# Low_Distortion_Oscillator_Amp2.net
KiCad netlist of a schematic drawn in Altium Designer
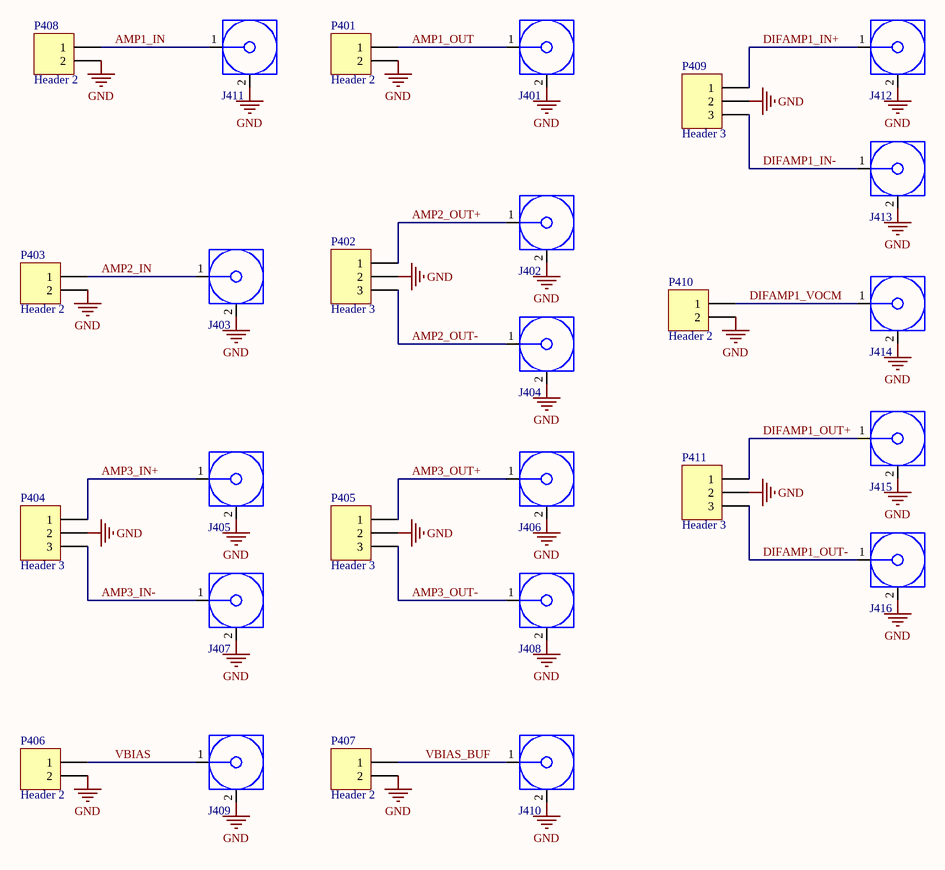
[diagram p0: Low Distortion Oscillator.Amp2.SchDoc]

(export (version "E")
  (design (tool "Eeschema 10.0.6"))
  (components
    (comp (ref "J401") (value "SMA") (footprint "SMA-2") (libsource (lib "carrot_lib") (part "SMA")))
    (comp (ref "J402") (value "SMA") (footprint "SMA-2") (libsource (lib "carrot_lib") (part "SMA")))
    (comp (ref "J403") (value "SMA") (footprint "SMA-2") (libsource (lib "carrot_lib") (part "SMA")))
    (comp (ref "J404") (value "SMA") (footprint "SMA-2") (libsource (lib "carrot_lib") (part "SMA")))
    (comp (ref "J405") (value "SMA") (footprint "SMA-2") (libsource (lib "carrot_lib") (part "SMA")))
    (comp (ref "J406") (value "SMA") (footprint "SMA-2") (libsource (lib "carrot_lib") (part "SMA")))
    (comp (ref "J407") (value "SMA") (footprint "SMA-2") (libsource (lib "carrot_lib") (part "SMA")))
    (comp (ref "J408") (value "SMA") (footprint "SMA-2") (libsource (lib "carrot_lib") (part "SMA")))
    (comp (ref "J409") (value "SMA") (footprint "SMA-2") (libsource (lib "carrot_lib") (part "SMA")))
    (comp (ref "J410") (value "SMA") (footprint "SMA-2") (libsource (lib "carrot_lib") (part "SMA")))
    (comp (ref "J411") (value "SMA") (footprint "SMA-2") (libsource (lib "carrot_lib") (part "SMA")))
    (comp (ref "J412") (value "SMA") (footprint "SMA-2") (libsource (lib "carrot_lib") (part "SMA")))
    (comp (ref "J413") (value "SMA") (footprint "SMA-2") (libsource (lib "carrot_lib") (part "SMA")))
    (comp (ref "J414") (value "SMA") (footprint "SMA-2") (libsource (lib "carrot_lib") (part "SMA")))
    (comp (ref "J415") (value "SMA") (footprint "SMA-2") (libsource (lib "carrot_lib") (part "SMA")))
    (comp (ref "J416") (value "SMA") (footprint "SMA-2") (libsource (lib "carrot_lib") (part "SMA")))
    (comp (ref "P401")
      (value "Header 2")
      (footprint "HDR1X2")
      (description "Header, 2-Pin")
      (libsource (lib "carrot_lib") (part "Header 2"))
    )
    (comp (ref "P402")
      (value "Header 3")
      (footprint "HDR1X3")
      (description "Header, 3-Pin")
      (libsource (lib "carrot_lib") (part "Header 3"))
    )
    (comp (ref "P403")
      (value "Header 2")
      (footprint "HDR1X2")
      (description "Header, 2-Pin")
      (libsource (lib "carrot_lib") (part "Header 2"))
    )
    (comp (ref "P404")
      (value "Header 3")
      (footprint "HDR1X3")
      (description "Header, 3-Pin")
      (libsource (lib "carrot_lib") (part "Header 3"))
    )
    (comp (ref "P405")
      (value "Header 3")
      (footprint "HDR1X3")
      (description "Header, 3-Pin")
      (libsource (lib "carrot_lib") (part "Header 3"))
    )
    (comp (ref "P406")
      (value "Header 2")
      (footprint "HDR1X2")
      (description "Header, 2-Pin")
      (libsource (lib "carrot_lib") (part "Header 2"))
    )
    (comp (ref "P407")
      (value "Header 2")
      (footprint "HDR1X2")
      (description "Header, 2-Pin")
      (libsource (lib "carrot_lib") (part "Header 2"))
    )
    (comp (ref "P408")
      (value "Header 2")
      (footprint "HDR1X2")
      (description "Header, 2-Pin")
      (libsource (lib "carrot_lib") (part "Header 2"))
    )
    (comp (ref "P409")
      (value "Header 3")
      (footprint "HDR1X3")
      (description "Header, 3-Pin")
      (libsource (lib "carrot_lib") (part "Header 3"))
    )
    (comp (ref "P410")
      (value "Header 2")
      (footprint "HDR1X2")
      (description "Header, 2-Pin")
      (libsource (lib "carrot_lib") (part "Header 2"))
    )
    (comp (ref "P411")
      (value "Header 3")
      (footprint "HDR1X3")
      (description "Header, 3-Pin")
      (libsource (lib "carrot_lib") (part "Header 3"))
    )
  )
  (nets
    (net (code "1") (name "/AMP1_IN") (class "Default")
      (node (ref "J411") (pin "1") (pinfunction "Signal_1") (pintype "power_in"))
      (node (ref "P408") (pin "1") (pinfunction "1_1") (pintype "passive"))
    )
    (net (code "2") (name "/AMP1_OUT") (class "Default")
      (node (ref "J401") (pin "1") (pinfunction "Signal_1") (pintype "power_in"))
      (node (ref "P401") (pin "1") (pinfunction "1_1") (pintype "passive"))
    )
    (net (code "3") (name "/AMP2_IN") (class "Default")
      (node (ref "J403") (pin "1") (pinfunction "Signal_1") (pintype "power_in"))
      (node (ref "P403") (pin "1") (pinfunction "1_1") (pintype "passive"))
    )
    (net (code "4") (name "/AMP2_OUT+") (class "Default")
      (node (ref "J402") (pin "1") (pinfunction "Signal_1") (pintype "power_in"))
      (node (ref "P402") (pin "1") (pinfunction "1_1") (pintype "passive"))
    )
    (net (code "5") (name "/AMP2_OUT-") (class "Default")
      (node (ref "J404") (pin "1") (pinfunction "Signal_1") (pintype "power_in"))
      (node (ref "P402") (pin "3") (pinfunction "3_3") (pintype "passive"))
    )
    (net (code "6") (name "/AMP3_IN+") (class "Default")
      (node (ref "J405") (pin "1") (pinfunction "Signal_1") (pintype "power_in"))
      (node (ref "P404") (pin "1") (pinfunction "1_1") (pintype "passive"))
    )
    (net (code "7") (name "/AMP3_IN-") (class "Default")
      (node (ref "J407") (pin "1") (pinfunction "Signal_1") (pintype "power_in"))
      (node (ref "P404") (pin "3") (pinfunction "3_3") (pintype "passive"))
    )
    (net (code "8") (name "/AMP3_OUT+") (class "Default")
      (node (ref "J406") (pin "1") (pinfunction "Signal_1") (pintype "power_in"))
      (node (ref "P405") (pin "1") (pinfunction "1_1") (pintype "passive"))
    )
    (net (code "9") (name "/AMP3_OUT-") (class "Default")
      (node (ref "J408") (pin "1") (pinfunction "Signal_1") (pintype "power_in"))
      (node (ref "P405") (pin "3") (pinfunction "3_3") (pintype "passive"))
    )
    (net (code "10") (name "/DIFAMP1_IN+") (class "Default")
      (node (ref "J412") (pin "1") (pinfunction "Signal_1") (pintype "power_in"))
      (node (ref "P409") (pin "1") (pinfunction "1_1") (pintype "passive"))
    )
    (net (code "11") (name "/DIFAMP1_IN-") (class "Default")
      (node (ref "J413") (pin "1") (pinfunction "Signal_1") (pintype "power_in"))
      (node (ref "P409") (pin "3") (pinfunction "3_3") (pintype "passive"))
    )
    (net (code "12") (name "/DIFAMP1_OUT+") (class "Default")
      (node (ref "J415") (pin "1") (pinfunction "Signal_1") (pintype "power_in"))
      (node (ref "P411") (pin "1") (pinfunction "1_1") (pintype "passive"))
    )
    (net (code "13") (name "/DIFAMP1_OUT-") (class "Default")
      (node (ref "J416") (pin "1") (pinfunction "Signal_1") (pintype "power_in"))
      (node (ref "P411") (pin "3") (pinfunction "3_3") (pintype "passive"))
    )
    (net (code "14") (name "/DIFAMP1_VOCM") (class "Default")
      (node (ref "J414") (pin "1") (pinfunction "Signal_1") (pintype "power_in"))
      (node (ref "P410") (pin "1") (pinfunction "1_1") (pintype "passive"))
    )
    (net (code "15") (name "/VBIAS") (class "Default")
      (node (ref "J409") (pin "1") (pinfunction "Signal_1") (pintype "power_in"))
      (node (ref "P406") (pin "1") (pinfunction "1_1") (pintype "passive"))
    )
    (net (code "16") (name "/VBIAS_BUF") (class "Default")
      (node (ref "J410") (pin "1") (pinfunction "Signal_1") (pintype "power_in"))
      (node (ref "P407") (pin "1") (pinfunction "1_1") (pintype "passive"))
    )
    (net (code "17") (name "GND") (class "Default")
      (node (ref "J401") (pin "2") (pinfunction "GND_2") (pintype "power_in"))
      (node (ref "J402") (pin "2") (pinfunction "GND_2") (pintype "power_in"))
      (node (ref "J403") (pin "2") (pinfunction "GND_2") (pintype "power_in"))
      (node (ref "J404") (pin "2") (pinfunction "GND_2") (pintype "power_in"))
      (node (ref "J405") (pin "2") (pinfunction "GND_2") (pintype "power_in"))
      (node (ref "J406") (pin "2") (pinfunction "GND_2") (pintype "power_in"))
      (node (ref "J407") (pin "2") (pinfunction "GND_2") (pintype "power_in"))
      (node (ref "J408") (pin "2") (pinfunction "GND_2") (pintype "power_in"))
      (node (ref "J409") (pin "2") (pinfunction "GND_2") (pintype "power_in"))
      (node (ref "J410") (pin "2") (pinfunction "GND_2") (pintype "power_in"))
      (node (ref "J411") (pin "2") (pinfunction "GND_2") (pintype "power_in"))
      (node (ref "J412") (pin "2") (pinfunction "GND_2") (pintype "power_in"))
      (node (ref "J413") (pin "2") (pinfunction "GND_2") (pintype "power_in"))
      (node (ref "J414") (pin "2") (pinfunction "GND_2") (pintype "power_in"))
      (node (ref "J415") (pin "2") (pinfunction "GND_2") (pintype "power_in"))
      (node (ref "J416") (pin "2") (pinfunction "GND_2") (pintype "power_in"))
      (node (ref "P401") (pin "2") (pinfunction "2_2") (pintype "passive"))
      (node (ref "P402") (pin "2") (pinfunction "2_2") (pintype "passive"))
      (node (ref "P403") (pin "2") (pinfunction "2_2") (pintype "passive"))
      (node (ref "P404") (pin "2") (pinfunction "2_2") (pintype "passive"))
      (node (ref "P405") (pin "2") (pinfunction "2_2") (pintype "passive"))
      (node (ref "P406") (pin "2") (pinfunction "2_2") (pintype "passive"))
      (node (ref "P407") (pin "2") (pinfunction "2_2") (pintype "passive"))
      (node (ref "P408") (pin "2") (pinfunction "2_2") (pintype "passive"))
      (node (ref "P409") (pin "2") (pinfunction "2_2") (pintype "passive"))
      (node (ref "P410") (pin "2") (pinfunction "2_2") (pintype "passive"))
      (node (ref "P411") (pin "2") (pinfunction "2_2") (pintype "passive"))
    )
  )
)
